# PowerSensor.net
KiCad netlist of a schematic drawn in EAGLE
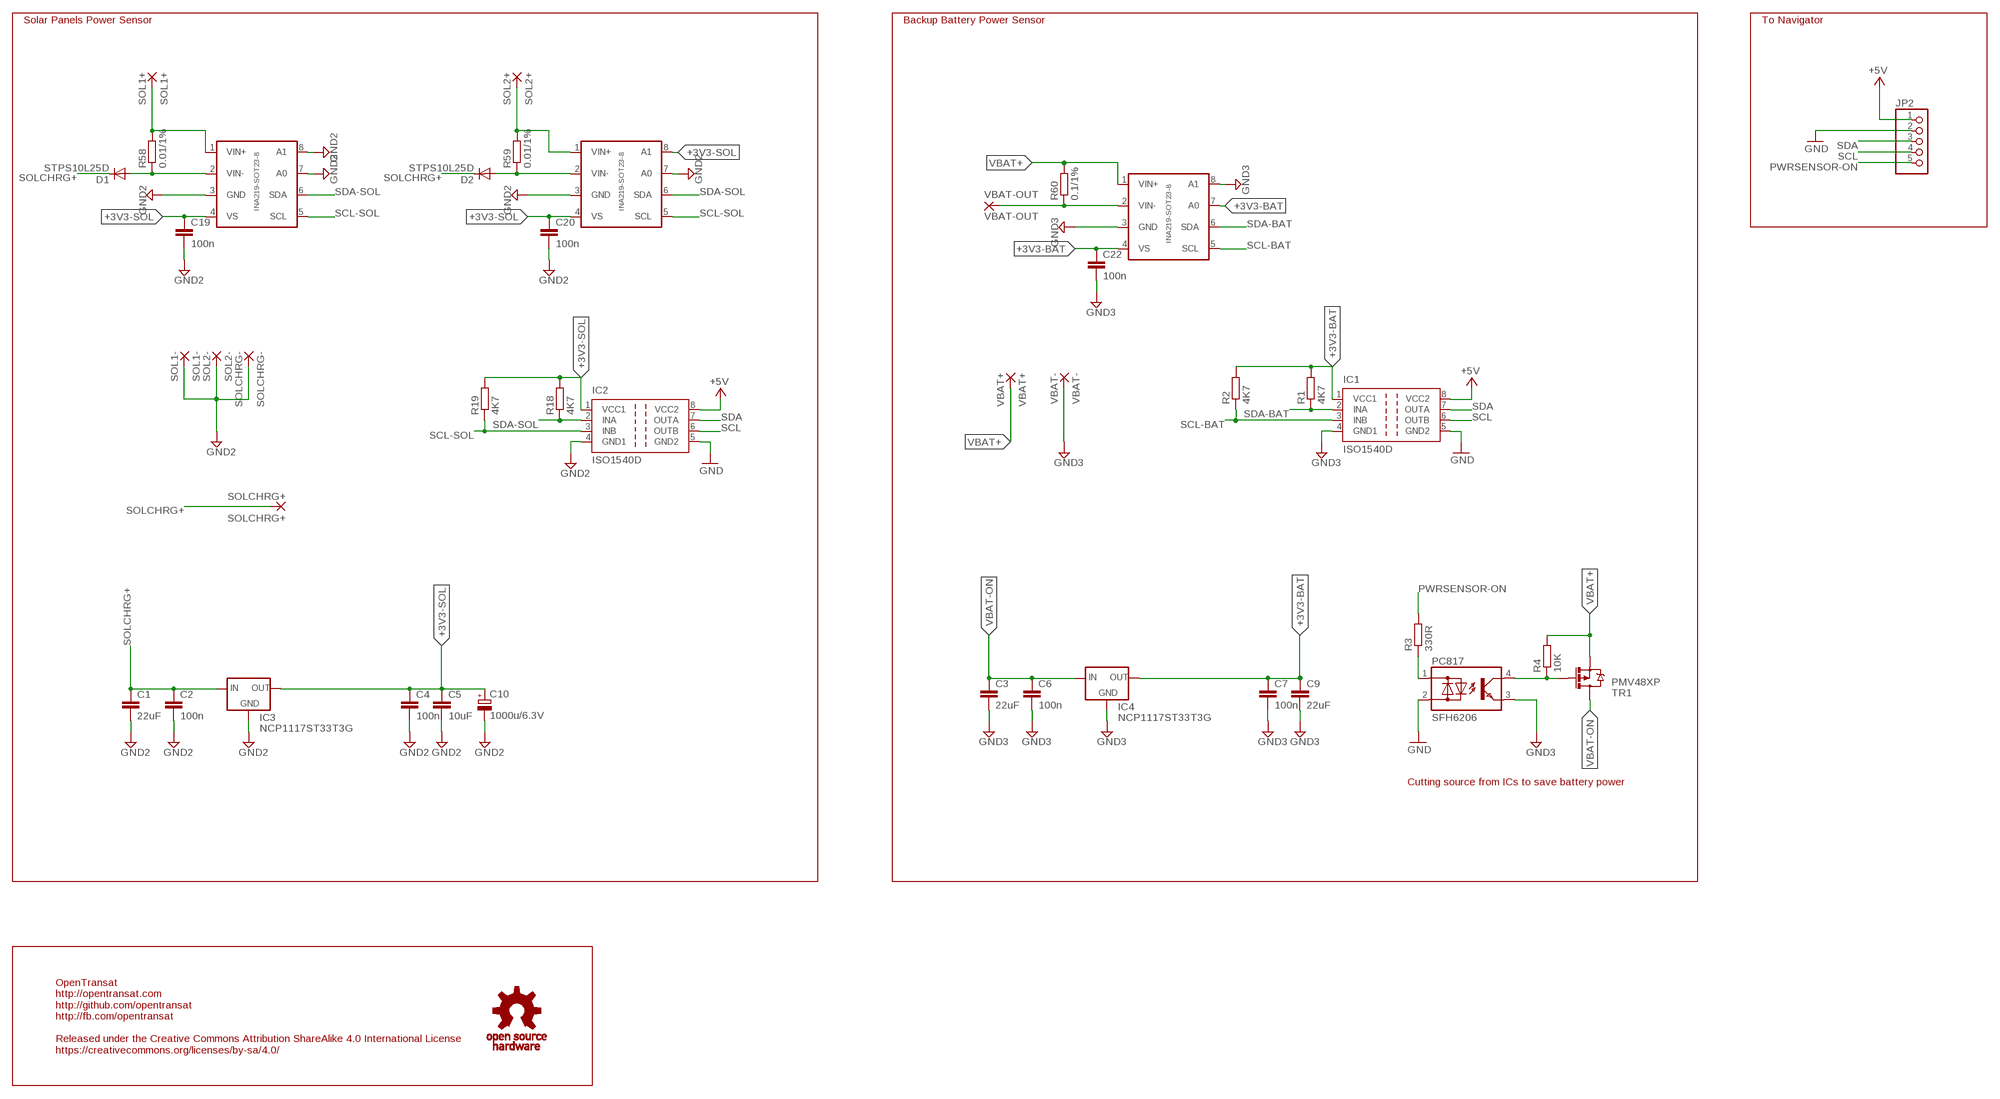
[diagram p0: schematic, sheet 1]

(export (version "E")
  (design (tool "Eeschema 10.0.6"))
  (components
    (comp (ref "C1")
      (value "22uF")
      (footprint "eagle-import:C1210")
      (libsource (lib "eagle-import") (part "C-EUC1210"))
    )
    (comp (ref "C2")
      (value "100n")
      (footprint "eagle-import:C0603")
      (libsource (lib "eagle-import") (part "C-EUC0603"))
    )
    (comp (ref "C3")
      (value "22uF")
      (footprint "eagle-import:C1210")
      (libsource (lib "eagle-import") (part "C-EUC1210"))
    )
    (comp (ref "C4")
      (value "100n")
      (footprint "eagle-import:C0603")
      (libsource (lib "eagle-import") (part "C-EUC0603"))
    )
    (comp (ref "C5")
      (value "10uF")
      (footprint "eagle-import:C1206")
      (libsource (lib "eagle-import") (part "C-EUC1206"))
    )
    (comp (ref "C6")
      (value "100n")
      (footprint "eagle-import:C0603")
      (libsource (lib "eagle-import") (part "C-EUC0603"))
    )
    (comp (ref "C7")
      (value "100n")
      (footprint "eagle-import:C0603")
      (libsource (lib "eagle-import") (part "C-EUC0603"))
    )
    (comp (ref "C9")
      (value "22uF")
      (footprint "eagle-import:C1210")
      (libsource (lib "eagle-import") (part "C-EUC1210"))
    )
    (comp (ref "C10")
      (value "1000u/6.3V")
      (footprint "eagle-import:E3,5-8")
      (libsource (lib "eagle-import") (part "CPOL-EUE3.5-8"))
    )
    (comp (ref "C19")
      (value "100n")
      (footprint "eagle-import:C0603")
      (libsource (lib "eagle-import") (part "C-EUC0603"))
    )
    (comp (ref "C20")
      (value "100n")
      (footprint "eagle-import:C0603")
      (libsource (lib "eagle-import") (part "C-EUC0603"))
    )
    (comp (ref "C22")
      (value "100n")
      (footprint "eagle-import:C0603")
      (libsource (lib "eagle-import") (part "C-EUC0603"))
    )
    (comp (ref "D1")
      (value "STPS10L25D")
      (footprint "eagle-import:TO220ACS")
      (libsource (lib "eagle-import") (part "DIODE-TO220V"))
    )
    (comp (ref "D2")
      (value "STPS10L25D")
      (footprint "eagle-import:TO220ACS")
      (libsource (lib "eagle-import") (part "DIODE-TO220V"))
    )
    (comp (ref "IC1")
      (value "ISO1540D")
      (footprint "eagle-import:SO-08")
      (fields (field (name "MPN") "ISO7220AD"))
      (libsource (lib "eagle-import") (part "ISO7220A"))
    )
    (comp (ref "IC2")
      (value "ISO1540D")
      (footprint "eagle-import:SO-08")
      (fields (field (name "MPN") "ISO7220AD"))
      (libsource (lib "eagle-import") (part "ISO7220A"))
    )
    (comp (ref "IC3")
      (value "NCP1117ST33T3G")
      (footprint "eagle-import:SOT223")
      (fields (field (name "MF") "Texas Instruments") (field (name "MPN") "LM1117MP-3.3"))
      (libsource (lib "eagle-import") (part "LM1117?-MP3.3"))
    )
    (comp (ref "IC4")
      (value "NCP1117ST33T3G")
      (footprint "eagle-import:SOT223")
      (fields (field (name "MF") "Texas Instruments") (field (name "MPN") "LM1117MP-3.3"))
      (libsource (lib "eagle-import") (part "LM1117?-MP3.3"))
    )
    (comp (ref "JP2")
      (value "PINHD-1X5")
      (footprint "eagle-import:1X05")
      (libsource (lib "eagle-import") (part "PINHD-1X5"))
    )
    (comp (ref "PC817")
      (value "SFH6206")
      (footprint "eagle-import:DIL4-SMD")
      (fields (field (name "MF") "VISHAY/TELEFUNKEN") (field (name "MPN") "SFH6206-3"))
      (libsource (lib "eagle-import") (part "SFH6206"))
    )
    (comp (ref "R1")
      (value "4K7")
      (footprint "eagle-import:R0603")
      (libsource (lib "eagle-import") (part "R-EU_R0603"))
    )
    (comp (ref "R2")
      (value "4K7")
      (footprint "eagle-import:R0603")
      (libsource (lib "eagle-import") (part "R-EU_R0603"))
    )
    (comp (ref "R3")
      (value "330R")
      (footprint "eagle-import:R0603")
      (libsource (lib "eagle-import") (part "R-EU_R0603"))
    )
    (comp (ref "R4")
      (value "10K")
      (footprint "eagle-import:R0603")
      (libsource (lib "eagle-import") (part "R-EU_R0603"))
    )
    (comp (ref "R18")
      (value "4K7")
      (footprint "eagle-import:R0603")
      (libsource (lib "eagle-import") (part "R-EU_R0603"))
    )
    (comp (ref "R19")
      (value "4K7")
      (footprint "eagle-import:R0603")
      (libsource (lib "eagle-import") (part "R-EU_R0603"))
    )
    (comp (ref "R58")
      (value "0.01/1%")
      (footprint "eagle-import:R2512")
      (libsource (lib "eagle-import") (part "R-EU_R2512"))
    )
    (comp (ref "R59")
      (value "0.01/1%")
      (footprint "eagle-import:R2512")
      (libsource (lib "eagle-import") (part "R-EU_R2512"))
    )
    (comp (ref "R60")
      (value "0.1/1%")
      (footprint "eagle-import:R2512")
      (libsource (lib "eagle-import") (part "R-EU_R2512"))
    )
    (comp (ref "SOL1+")
      (value "SOL1+")
      (footprint "eagle-import:SMD5,08-10,16")
      (libsource (lib "eagle-import") (part "SMD10"))
    )
    (comp (ref "SOL1-")
      (value "SOL1-")
      (footprint "eagle-import:SMD5,08-10,16")
      (libsource (lib "eagle-import") (part "SMD10"))
    )
    (comp (ref "SOL2+")
      (value "SOL2+")
      (footprint "eagle-import:SMD5,08-10,16")
      (libsource (lib "eagle-import") (part "SMD10"))
    )
    (comp (ref "SOL2-")
      (value "SOL2-")
      (footprint "eagle-import:SMD5,08-10,16")
      (libsource (lib "eagle-import") (part "SMD10"))
    )
    (comp (ref "SOLCHRG+")
      (value "SOLCHRG+")
      (footprint "eagle-import:SMD5,08-10,16")
      (libsource (lib "eagle-import") (part "SMD10"))
    )
    (comp (ref "SOLCHRG-")
      (value "SOLCHRG-")
      (footprint "eagle-import:SMD5,08-10,16")
      (libsource (lib "eagle-import") (part "SMD10"))
    )
    (comp (ref "TR1")
      (value "PMV48XP")
      (footprint "eagle-import:SOT23-3")
      (libsource (lib "eagle-import") (part "MOSFET-PCHANNEL_SOT23-3"))
    )
    (comp (ref "U$1")
      (value "INA219-SOT23-8")
      (footprint "eagle-import:SOT23-8")
      (libsource (lib "eagle-import") (part "INA219-SOT23-8"))
    )
    (comp (ref "U$2")
      (value "OSHW")
      (footprint "eagle-import:OSHWM")
      (libsource (lib "eagle-import") (part "OSHW"))
    )
    (comp (ref "U$4")
      (value "INA219-SOT23-8")
      (footprint "eagle-import:SOT23-8")
      (libsource (lib "eagle-import") (part "INA219-SOT23-8"))
    )
    (comp (ref "U$5")
      (value "INA219-SOT23-8")
      (footprint "eagle-import:SOT23-8")
      (libsource (lib "eagle-import") (part "INA219-SOT23-8"))
    )
    (comp (ref "VBAT+")
      (value "VBAT+")
      (footprint "eagle-import:SMD2,54-5,08")
      (libsource (lib "eagle-import") (part "WIREPADSMD2,54-5,08"))
    )
    (comp (ref "VBAT-")
      (value "VBAT-")
      (footprint "eagle-import:SMD2,54-5,08")
      (libsource (lib "eagle-import") (part "WIREPADSMD2,54-5,08"))
    )
    (comp (ref "VBAT-OUT")
      (value "VBAT-OUT")
      (footprint "eagle-import:SMD2,54-5,08")
      (libsource (lib "eagle-import") (part "WIREPADSMD2,54-5,08"))
    )
  )
  (nets
    (net (code "1") (name "+3V3-BAT") (class "Default")
      (node (ref "C22") (pin "1") (pinfunction "1_1") (pintype "passive"))
      (node (ref "C7") (pin "1") (pinfunction "1_1") (pintype "passive"))
      (node (ref "C9") (pin "1") (pinfunction "1_1") (pintype "passive"))
      (node (ref "IC1") (pin "1") (pinfunction "VCC1_1") (pintype "power_in"))
      (node (ref "IC4") (pin "2") (pinfunction "OUT_2") (pintype "passive"))
      (node (ref "IC4") (pin "4") (pinfunction "OUT_4") (pintype "passive"))
      (node (ref "R1") (pin "2") (pinfunction "2_2") (pintype "passive"))
      (node (ref "R2") (pin "2") (pinfunction "2_2") (pintype "passive"))
      (node (ref "U$5") (pin "4") (pinfunction "VS_4") (pintype "power_in"))
      (node (ref "U$5") (pin "7") (pinfunction "A0_7") (pintype "input"))
    )
    (net (code "2") (name "+3V3-SOL") (class "Default")
      (node (ref "C10") (pin "+") (pinfunction "+_+") (pintype "passive"))
      (node (ref "C19") (pin "1") (pinfunction "1_1") (pintype "passive"))
      (node (ref "C20") (pin "1") (pinfunction "1_1") (pintype "passive"))
      (node (ref "C4") (pin "1") (pinfunction "1_1") (pintype "passive"))
      (node (ref "C5") (pin "1") (pinfunction "1_1") (pintype "passive"))
      (node (ref "IC2") (pin "1") (pinfunction "VCC1_1") (pintype "power_in"))
      (node (ref "IC3") (pin "2") (pinfunction "OUT_2") (pintype "passive"))
      (node (ref "IC3") (pin "4") (pinfunction "OUT_4") (pintype "passive"))
      (node (ref "R18") (pin "2") (pinfunction "2_2") (pintype "passive"))
      (node (ref "R19") (pin "2") (pinfunction "2_2") (pintype "passive"))
      (node (ref "U$1") (pin "4") (pinfunction "VS_4") (pintype "power_in"))
      (node (ref "U$4") (pin "4") (pinfunction "VS_4") (pintype "power_in"))
      (node (ref "U$4") (pin "8") (pinfunction "A1_8") (pintype "input"))
    )
    (net (code "3") (name "+5V") (class "Default")
      (node (ref "IC1") (pin "8") (pinfunction "VCC2_8") (pintype "power_in"))
      (node (ref "IC2") (pin "8") (pinfunction "VCC2_8") (pintype "power_in"))
      (node (ref "JP2") (pin "1") (pinfunction "1_1") (pintype "passive"))
    )
    (net (code "4") (name "/PWRSENSOR-ON") (class "Default")
      (node (ref "JP2") (pin "5") (pinfunction "5_5") (pintype "passive"))
      (node (ref "R3") (pin "2") (pinfunction "2_2") (pintype "passive"))
    )
    (net (code "5") (name "/SCL") (class "Default")
      (node (ref "IC1") (pin "6") (pinfunction "OUTB_6") (pintype "output"))
      (node (ref "IC2") (pin "6") (pinfunction "OUTB_6") (pintype "output"))
      (node (ref "JP2") (pin "4") (pinfunction "4_4") (pintype "passive"))
    )
    (net (code "6") (name "/SCL-BAT") (class "Default")
      (node (ref "IC1") (pin "3") (pinfunction "INB_3") (pintype "input"))
      (node (ref "R2") (pin "1") (pinfunction "1_1") (pintype "passive"))
      (node (ref "U$5") (pin "5") (pinfunction "SCL_5") (pintype "bidirectional"))
    )
    (net (code "7") (name "/SCL-SOL") (class "Default")
      (node (ref "IC2") (pin "3") (pinfunction "INB_3") (pintype "input"))
      (node (ref "R19") (pin "1") (pinfunction "1_1") (pintype "passive"))
      (node (ref "U$1") (pin "5") (pinfunction "SCL_5") (pintype "bidirectional"))
      (node (ref "U$4") (pin "5") (pinfunction "SCL_5") (pintype "bidirectional"))
    )
    (net (code "8") (name "/SDA") (class "Default")
      (node (ref "IC1") (pin "7") (pinfunction "OUTA_7") (pintype "output"))
      (node (ref "IC2") (pin "7") (pinfunction "OUTA_7") (pintype "output"))
      (node (ref "JP2") (pin "3") (pinfunction "3_3") (pintype "passive"))
    )
    (net (code "9") (name "/SDA-BAT") (class "Default")
      (node (ref "IC1") (pin "2") (pinfunction "INA_2") (pintype "input"))
      (node (ref "R1") (pin "1") (pinfunction "1_1") (pintype "passive"))
      (node (ref "U$5") (pin "6") (pinfunction "SDA_6") (pintype "bidirectional"))
    )
    (net (code "10") (name "/SDA-SOL") (class "Default")
      (node (ref "IC2") (pin "2") (pinfunction "INA_2") (pintype "input"))
      (node (ref "R18") (pin "1") (pinfunction "1_1") (pintype "passive"))
      (node (ref "U$1") (pin "6") (pinfunction "SDA_6") (pintype "bidirectional"))
      (node (ref "U$4") (pin "6") (pinfunction "SDA_6") (pintype "bidirectional"))
    )
    (net (code "11") (name "/SOLCHRG+") (class "Default")
      (node (ref "C1") (pin "1") (pinfunction "1_1") (pintype "passive"))
      (node (ref "C2") (pin "1") (pinfunction "1_1") (pintype "passive"))
      (node (ref "D1") (pin "C") (pinfunction "C_C") (pintype "passive"))
      (node (ref "D2") (pin "C") (pinfunction "C_C") (pintype "passive"))
      (node (ref "IC3") (pin "3") (pinfunction "IN_3") (pintype "input"))
      (node (ref "SOLCHRG+") (pin "1") (pinfunction "P_1") (pintype "passive"))
    )
    (net (code "12") (name "GND") (class "Default")
      (node (ref "IC1") (pin "5") (pinfunction "GND2_5") (pintype "power_in"))
      (node (ref "IC2") (pin "5") (pinfunction "GND2_5") (pintype "power_in"))
      (node (ref "JP2") (pin "2") (pinfunction "2_2") (pintype "passive"))
      (node (ref "PC817") (pin "2") (pinfunction "AC2_2") (pintype "passive"))
    )
    (net (code "13") (name "GND2") (class "Default")
      (node (ref "C1") (pin "2") (pinfunction "2_2") (pintype "passive"))
      (node (ref "C10") (pin "-") (pinfunction "-_-") (pintype "passive"))
      (node (ref "C19") (pin "2") (pinfunction "2_2") (pintype "passive"))
      (node (ref "C2") (pin "2") (pinfunction "2_2") (pintype "passive"))
      (node (ref "C20") (pin "2") (pinfunction "2_2") (pintype "passive"))
      (node (ref "C4") (pin "2") (pinfunction "2_2") (pintype "passive"))
      (node (ref "C5") (pin "2") (pinfunction "2_2") (pintype "passive"))
      (node (ref "IC2") (pin "4") (pinfunction "GND1_4") (pintype "power_in"))
      (node (ref "IC3") (pin "1") (pinfunction "GND_1") (pintype "input"))
      (node (ref "SOL1-") (pin "1") (pinfunction "P_1") (pintype "passive"))
      (node (ref "SOL2-") (pin "1") (pinfunction "P_1") (pintype "passive"))
      (node (ref "SOLCHRG-") (pin "1") (pinfunction "P_1") (pintype "passive"))
      (node (ref "U$1") (pin "3") (pinfunction "GND_3") (pintype "power_in"))
      (node (ref "U$1") (pin "7") (pinfunction "A0_7") (pintype "input"))
      (node (ref "U$1") (pin "8") (pinfunction "A1_8") (pintype "input"))
      (node (ref "U$4") (pin "3") (pinfunction "GND_3") (pintype "power_in"))
      (node (ref "U$4") (pin "7") (pinfunction "A0_7") (pintype "input"))
    )
    (net (code "14") (name "GND3") (class "Default")
      (node (ref "C22") (pin "2") (pinfunction "2_2") (pintype "passive"))
      (node (ref "C3") (pin "2") (pinfunction "2_2") (pintype "passive"))
      (node (ref "C6") (pin "2") (pinfunction "2_2") (pintype "passive"))
      (node (ref "C7") (pin "2") (pinfunction "2_2") (pintype "passive"))
      (node (ref "C9") (pin "2") (pinfunction "2_2") (pintype "passive"))
      (node (ref "IC1") (pin "4") (pinfunction "GND1_4") (pintype "power_in"))
      (node (ref "IC4") (pin "1") (pinfunction "GND_1") (pintype "input"))
      (node (ref "PC817") (pin "3") (pinfunction "E_3") (pintype "passive"))
      (node (ref "U$5") (pin "3") (pinfunction "GND_3") (pintype "power_in"))
      (node (ref "U$5") (pin "8") (pinfunction "A1_8") (pintype "input"))
      (node (ref "VBAT-") (pin "1") (pinfunction "P_1") (pintype "passive"))
    )
    (net (code "15") (name "Net-(PC817-AC1)") (class "Default")
      (node (ref "PC817") (pin "1") (pinfunction "AC1_1") (pintype "passive"))
      (node (ref "R3") (pin "1") (pinfunction "1_1") (pintype "passive"))
    )
    (net (code "16") (name "Net-(PC817-C)") (class "Default")
      (node (ref "PC817") (pin "4") (pinfunction "C_4") (pintype "passive"))
      (node (ref "R4") (pin "1") (pinfunction "1_1") (pintype "passive"))
      (node (ref "TR1") (pin "1") (pinfunction "G_1") (pintype "passive"))
    )
    (net (code "17") (name "Net-(SOL1+-P)") (class "Default")
      (node (ref "R58") (pin "2") (pinfunction "2_2") (pintype "passive"))
      (node (ref "SOL1+") (pin "1") (pinfunction "P_1") (pintype "passive"))
      (node (ref "U$1") (pin "1") (pinfunction "VIN+_1") (pintype "input"))
    )
    (net (code "18") (name "Net-(SOL2+-P)") (class "Default")
      (node (ref "R59") (pin "2") (pinfunction "2_2") (pintype "passive"))
      (node (ref "SOL2+") (pin "1") (pinfunction "P_1") (pintype "passive"))
      (node (ref "U$4") (pin "1") (pinfunction "VIN+_1") (pintype "input"))
    )
    (net (code "19") (name "Net-(U$1-VIN-)") (class "Default")
      (node (ref "D1") (pin "A") (pinfunction "A_A") (pintype "passive"))
      (node (ref "R58") (pin "1") (pinfunction "1_1") (pintype "passive"))
      (node (ref "U$1") (pin "2") (pinfunction "VIN-_2") (pintype "input"))
    )
    (net (code "20") (name "Net-(U$4-VIN-)") (class "Default")
      (node (ref "D2") (pin "A") (pinfunction "A_A") (pintype "passive"))
      (node (ref "R59") (pin "1") (pinfunction "1_1") (pintype "passive"))
      (node (ref "U$4") (pin "2") (pinfunction "VIN-_2") (pintype "input"))
    )
    (net (code "21") (name "Net-(U$5-VIN-)") (class "Default")
      (node (ref "R60") (pin "1") (pinfunction "1_1") (pintype "passive"))
      (node (ref "U$5") (pin "2") (pinfunction "VIN-_2") (pintype "input"))
      (node (ref "VBAT-OUT") (pin "1") (pinfunction "P_1") (pintype "passive"))
    )
    (net (code "22") (name "VBAT+") (class "Default")
      (node (ref "R4") (pin "2") (pinfunction "2_2") (pintype "passive"))
      (node (ref "R60") (pin "2") (pinfunction "2_2") (pintype "passive"))
      (node (ref "TR1") (pin "2") (pinfunction "S_2") (pintype "passive"))
      (node (ref "U$5") (pin "1") (pinfunction "VIN+_1") (pintype "input"))
      (node (ref "VBAT+") (pin "1") (pinfunction "P_1") (pintype "passive"))
    )
    (net (code "23") (name "VBAT-ON") (class "Default")
      (node (ref "C3") (pin "1") (pinfunction "1_1") (pintype "passive"))
      (node (ref "C6") (pin "1") (pinfunction "1_1") (pintype "passive"))
      (node (ref "IC4") (pin "3") (pinfunction "IN_3") (pintype "input"))
      (node (ref "TR1") (pin "3") (pinfunction "D_3") (pintype "passive"))
    )
  )
)
